# EC06-IDC_6-pin_Castellated_Board-Edge_Co.net
KiCad netlist of a schematic drawn in Altium Designer
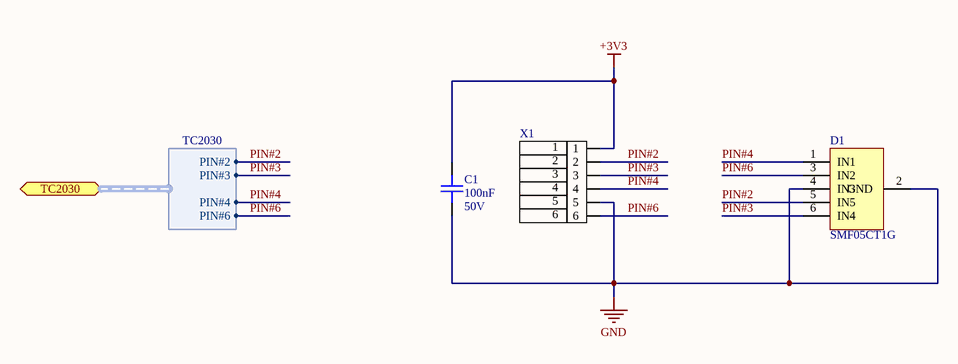
[diagram p0: EC06-IDC_6-pin_Castellated_Board-Edge_Connector.SchDoc]

(export (version "E")
  (design (tool "Eeschema 10.0.6"))
  (components
    (comp (ref "C1")
      (value "CAP CER 0.1UF 50V X7R 0402")
      (footprint "C0402")
      (description "0.1µF ±10% 50V Ceramic Capacitor X7R 0402 (1005 Metric)")
      (fields
        (field (name "MANUFACTURER") "TDK")
        (field (name "MANUFACTURER PART NUMBER") "CGA2B3X7R1H104K050BB")
        (field (name "CAPACITANCE") "100nF")
        (field (name "VOLTAGE") "50V")
      )
      (libsource (lib "capacitors_smd") (part "CAP CER 0.1UF 50V X7R 0402"))
    )
    (comp (ref "D1")
      (value "SMF05CT1G")
      (footprint "SOT363_SOP65P210X265-6N")
      (description "12.5V Clamp 8A (8/20µs) Ipp Tvs Diode Surface Mount SC-88/SC70-6/SOT-363")
      (fields (field (name "MANUFACTURER") "ON Semiconductor"))
      (libsource (lib "diodes_tvs") (part "TVS DIODE 5V 12.5V 5CH SC88"))
    )
    (comp (ref "X1")
      (value "~")
      (footprint "EC06-IDC")
      (description "6-pin Edge-Connect™ connector to 6-pin 0.1″ pitch female IDC.")
      (fields
        (field (name "PIN_1") "1")
        (field (name "PIN_2") "2")
        (field (name "PIN_6") "6")
        (field (name "PIN_3") "3")
        (field (name "PIN_4") "4")
        (field (name "PIN_5") "5")
      )
      (libsource (lib "connectors_TAG-Connect") (part "EC06-IDC 6-pin Castellated Board-Edge Connector"))
    )
  )
  (nets
    (net (code "2") (name "+3V3") (class "Default")
      (node (ref "C1") (pin "2") (pinfunction "2_2") (pintype "passive"))
      (node (ref "X1") (pin "1") (pinfunction "1_1") (pintype "passive"))
    )
    (net (code "3") (name "/PIN#2") (class "Default")
      (node (ref "D1") (pin "5") (pinfunction "IN5_5") (pintype "passive"))
      (node (ref "X1") (pin "2") (pinfunction "2_2") (pintype "passive"))
    )
    (net (code "4") (name "/PIN#3") (class "Default")
      (node (ref "D1") (pin "6") (pinfunction "IN4_6") (pintype "passive"))
      (node (ref "X1") (pin "3") (pinfunction "3_3") (pintype "passive"))
    )
    (net (code "5") (name "/PIN#4") (class "Default")
      (node (ref "D1") (pin "1") (pinfunction "IN1_1") (pintype "passive"))
      (node (ref "X1") (pin "4") (pinfunction "4_4") (pintype "passive"))
    )
    (net (code "6") (name "/PIN#6") (class "Default")
      (node (ref "D1") (pin "3") (pinfunction "IN2_3") (pintype "passive"))
      (node (ref "X1") (pin "6") (pinfunction "6_6") (pintype "passive"))
    )
    (net (code "8") (name "GND") (class "Default")
      (node (ref "C1") (pin "1") (pinfunction "1_1") (pintype "passive"))
      (node (ref "D1") (pin "2") (pinfunction "GND_2") (pintype "power_in"))
      (node (ref "D1") (pin "4") (pinfunction "IN3_4") (pintype "passive"))
      (node (ref "X1") (pin "5") (pinfunction "5_5") (pintype "passive"))
    )
  )
)
